# RADC-CANBUS-S03-V00.net
KiCad netlist of a schematic drawn in Altium Designer
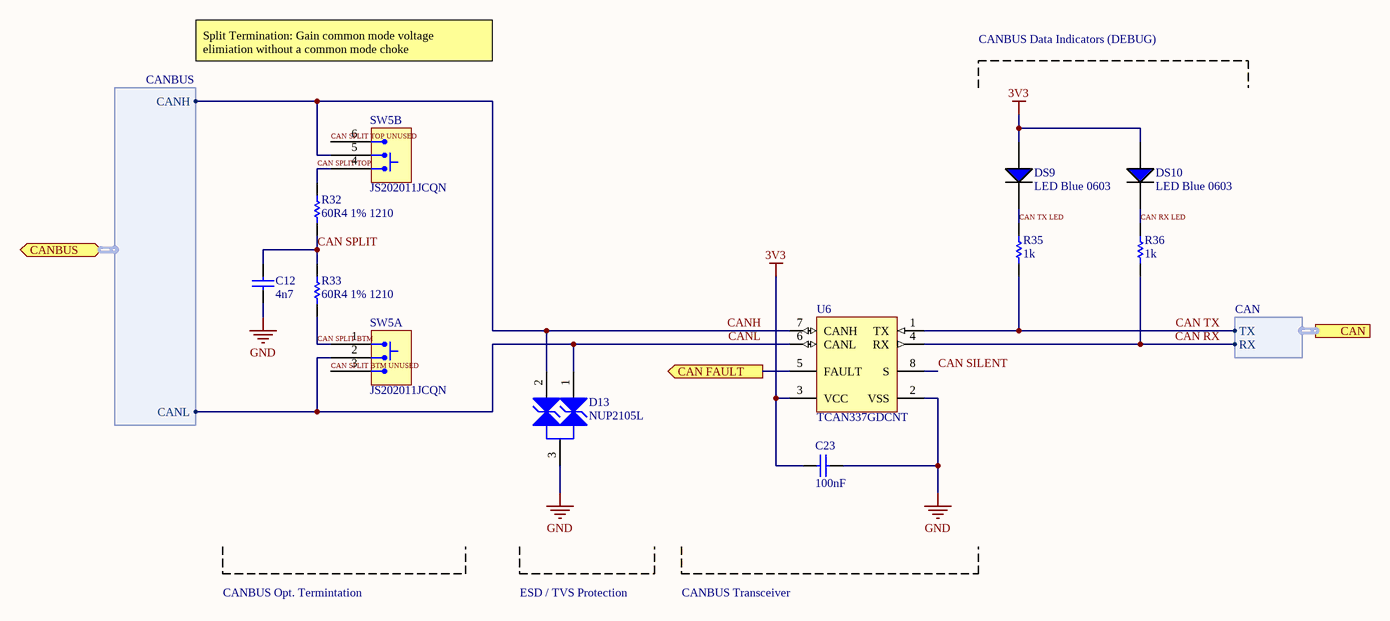
[diagram p0: RADC-CANBUS-S03-V00.SchDoc]

(export (version "E")
  (design (tool "Eeschema 10.0.6"))
  (components
    (comp (ref "C12")
      (value "4n7")
      (footprint "Cap_Ceramic_0603")
      (description "Capacitor, Ceramic, SMD, 4n7, 50V, 5%, X7R, 0603")
      (libsource (lib "StandardCapacitors") (part "4n7 50V 5% X7R 0603"))
    )
    (comp (ref "C23")
      (value "100nF")
      (footprint "Cap_Ceramic_0603")
      (description "Capacitor, Ceramic, SMD, 100nF, 50V, 5%, X7R, 0603")
      (libsource (lib "StandardCapacitors") (part "100nF 50V 5% X7R 0603"))
    )
    (comp (ref "D13")
      (value "NUP2105L")
      (footprint "NUP2105L")
      (libsource (lib "QUTMS_CANLibrary") (part "NUP2105L"))
    )
    (comp (ref "DS9")
      (value "LED Blue 0603")
      (footprint "LED BLUE 0603")
      (libsource (lib "QUTMS_LEDLibrary") (part "LED BLUE 0603"))
    )
    (comp (ref "DS10")
      (value "LED Blue 0603")
      (footprint "LED BLUE 0603")
      (libsource (lib "QUTMS_LEDLibrary") (part "LED BLUE 0603"))
    )
    (comp (ref "R32")
      (value "60R4 1% 1210")
      (footprint "Res_ThinFilm_1210")
      (description "Resistor, SMD, 60R4, 0.25W, 1%, 1210")
      (libsource (lib "StandardResistors") (part "60R4 1% 1210"))
    )
    (comp (ref "R33")
      (value "60R4 1% 1210")
      (footprint "Res_ThinFilm_1210")
      (description "Resistor, SMD, 60R4, 0.25W, 1%, 1210")
      (libsource (lib "StandardResistors") (part "60R4 1% 1210"))
    )
    (comp (ref "R35")
      (value "1k")
      (footprint "Res_ThinFilm_0603")
      (description "Resistor, SMD, 1k, 0.1W, 5%, 0603")
      (libsource (lib "StandardResistors") (part "1k 5% 0603"))
    )
    (comp (ref "R36")
      (value "1k")
      (footprint "Res_ThinFilm_0603")
      (description "Resistor, SMD, 1k, 0.1W, 5%, 0603")
      (libsource (lib "StandardResistors") (part "1k 5% 0603"))
    )
    (comp (ref "SW5")
      (value "JS202011JCQN")
      (footprint "JS202011JCQN")
      (libsource (lib "") (part "SLIDE DPDT JS202011JCQN_1"))
    )
    (comp (ref "U6")
      (value "TCAN337GDCNT")
      (footprint "SOT-23-8")
      (description "1/1 Transceiver CANbus SOT-23-8")
      (libsource (lib "QUTMS_CANLibrary") (part "TCAN337GDCNT"))
    )
  )
  (nets
    (net (code "3") (name "/CAN FAULT") (class "Default")
      (node (ref "U6") (pin "5") (pinfunction "FAULT_5") (pintype "passive"))
    )
    (net (code "4") (name "/CAN RX") (class "Default")
      (node (ref "R36") (pin "1") (pinfunction "1_1") (pintype "passive"))
      (node (ref "U6") (pin "4") (pinfunction "RX_4") (pintype "output"))
    )
    (net (code "5") (name "/CAN RX LED") (class "Default")
      (node (ref "DS10") (pin "2") (pinfunction "C_2") (pintype "passive"))
      (node (ref "R36") (pin "2") (pinfunction "2_2") (pintype "passive"))
    )
    (net (code "6") (name "/CAN SILENT") (class "Default")
      (node (ref "U6") (pin "8") (pinfunction "S_8") (pintype "passive"))
    )
    (net (code "7") (name "/CAN SPLIT") (class "Default")
      (node (ref "C12") (pin "2") (pinfunction "2_2") (pintype "passive"))
      (node (ref "R32") (pin "1") (pinfunction "1_1") (pintype "passive"))
      (node (ref "R33") (pin "2") (pinfunction "2_2") (pintype "passive"))
    )
    (net (code "8") (name "/CAN SPLIT BTM") (class "Default")
      (node (ref "R33") (pin "1") (pinfunction "1_1") (pintype "passive"))
      (node (ref "SW5") (pin "1") (pinfunction "1_1") (pintype "passive"))
    )
    (net (code "9") (name "/CAN SPLIT BTM UNUSED") (class "Default")
      (node (ref "SW5") (pin "3") (pinfunction "3_3") (pintype "passive"))
    )
    (net (code "10") (name "/CAN SPLIT TOP") (class "Default")
      (node (ref "R32") (pin "2") (pinfunction "2_2") (pintype "passive"))
      (node (ref "SW5") (pin "4") (pinfunction "4_4") (pintype "passive"))
    )
    (net (code "11") (name "/CAN SPLIT TOP UNUSED") (class "Default")
      (node (ref "SW5") (pin "6") (pinfunction "6_6") (pintype "passive"))
    )
    (net (code "12") (name "/CAN TX") (class "Default")
      (node (ref "R35") (pin "1") (pinfunction "1_1") (pintype "passive"))
      (node (ref "U6") (pin "1") (pinfunction "TX_1") (pintype "input"))
    )
    (net (code "13") (name "/CAN TX LED") (class "Default")
      (node (ref "DS9") (pin "2") (pinfunction "C_2") (pintype "passive"))
      (node (ref "R35") (pin "2") (pinfunction "2_2") (pintype "passive"))
    )
    (net (code "14") (name "/CANH") (class "Default")
      (node (ref "D13") (pin "2") (pinfunction "2_2") (pintype "passive"))
      (node (ref "SW5") (pin "5") (pinfunction "5_5") (pintype "passive"))
      (node (ref "U6") (pin "7") (pinfunction "CANH_7") (pintype "bidirectional"))
    )
    (net (code "15") (name "/CANL") (class "Default")
      (node (ref "D13") (pin "1") (pinfunction "1_1") (pintype "passive"))
      (node (ref "SW5") (pin "2") (pinfunction "2_2") (pintype "passive"))
      (node (ref "U6") (pin "6") (pinfunction "CANL_6") (pintype "bidirectional"))
    )
    (net (code "18") (name "3V3") (class "Default")
      (node (ref "C23") (pin "1") (pinfunction "1_1") (pintype "passive"))
      (node (ref "DS10") (pin "1") (pinfunction "A_1") (pintype "passive"))
      (node (ref "DS9") (pin "1") (pinfunction "A_1") (pintype "passive"))
      (node (ref "U6") (pin "3") (pinfunction "VCC_3") (pintype "passive"))
    )
    (net (code "19") (name "GND") (class "Default")
      (node (ref "C12") (pin "1") (pinfunction "1_1") (pintype "passive"))
      (node (ref "C23") (pin "2") (pinfunction "2_2") (pintype "passive"))
      (node (ref "D13") (pin "3") (pinfunction "3_3") (pintype "passive"))
      (node (ref "U6") (pin "2") (pinfunction "VSS_2") (pintype "passive"))
    )
  )
)
